# PowerBoard_v9.net
KiCad netlist of a schematic drawn in EAGLE
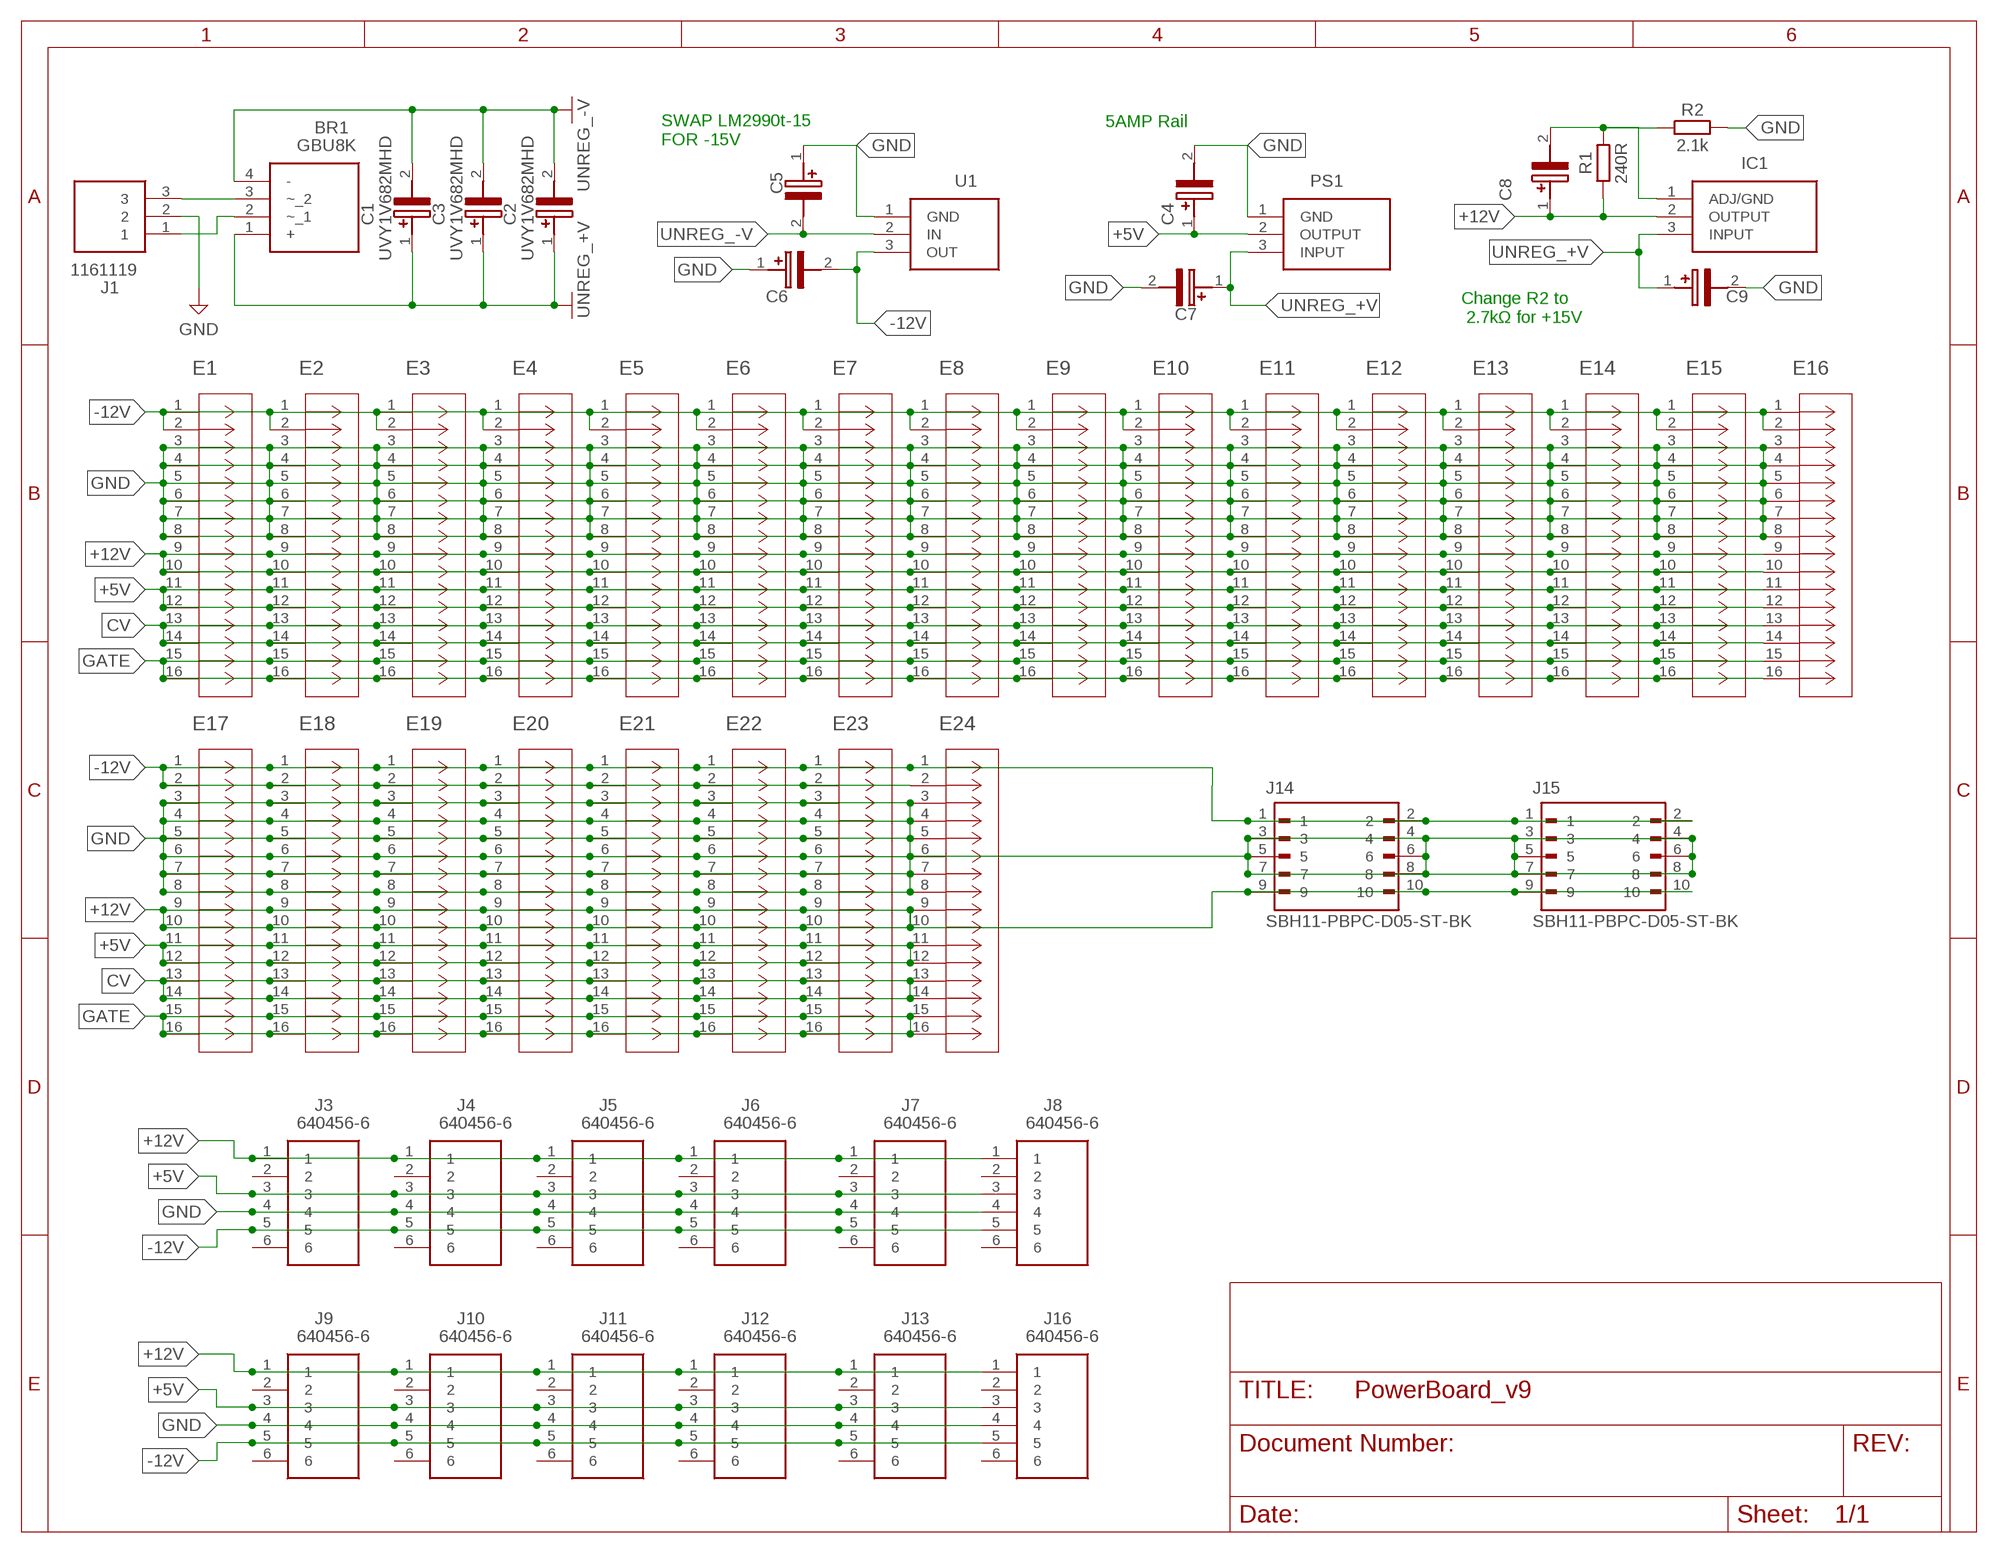
[diagram p0: schematic, sheet 1]

(export (version "E")
  (design (tool "Eeschema 10.0.6"))
  (components
    (comp (ref "BR1")
      (value "GBU8K")
      (footprint "eagle-import:GBU8K")
      (fields (field (name "MOUSER_PART_NUMBER") "512-GBU8K"))
      (libsource (lib "eagle-import") (part "GBU8K"))
    )
    (comp (ref "C1")
      (value "UVY1V682MHD")
      (footprint "eagle-import:CAPPRD750W80D1825H4200")
      (fields (field (name "MOUSER_PART_NUMBER") "647-UVY1V682MHD"))
      (libsource (lib "eagle-import") (part "UVY1V682MHD"))
    )
    (comp (ref "C2")
      (value "UVY1V682MHD")
      (footprint "eagle-import:CAPPRD750W80D1825H4200")
      (fields (field (name "MOUSER_PART_NUMBER") "647-UVY1V682MHD"))
      (libsource (lib "eagle-import") (part "UVY1V682MHD"))
    )
    (comp (ref "C3")
      (value "UVY1V682MHD")
      (footprint "eagle-import:CAPPRD750W80D1825H4200")
      (fields (field (name "MOUSER_PART_NUMBER") "647-UVY1V682MHD"))
      (libsource (lib "eagle-import") (part "UVY1V682MHD"))
    )
    (comp (ref "C4")
      (value "UEP1V101MPD")
      (footprint "eagle-import:CAPPRD500W60D1025H1750")
      (fields (field (name "MOUSER_PART_NUMBER") "647-UEP1V101MPD"))
      (libsource (lib "eagle-import") (part "UEP1V101MPD"))
    )
    (comp (ref "C5")
      (value "UEP1V101MPD")
      (footprint "eagle-import:CAPPRD500W60D1025H1750")
      (fields (field (name "MOUSER_PART_NUMBER") "647-UEP1V101MPD"))
      (libsource (lib "eagle-import") (part "UEP1V101MPD"))
    )
    (comp (ref "C6")
      (value "UEP1V101MPD")
      (footprint "eagle-import:CAPPRD500W60D1025H1750")
      (fields (field (name "MOUSER_PART_NUMBER") "647-UEP1V101MPD"))
      (libsource (lib "eagle-import") (part "UEP1V101MPD"))
    )
    (comp (ref "C7")
      (value "UEP1V101MPD")
      (footprint "eagle-import:CAPPRD500W60D1025H1750")
      (fields (field (name "MOUSER_PART_NUMBER") "647-UEP1V101MPD"))
      (libsource (lib "eagle-import") (part "UEP1V101MPD"))
    )
    (comp (ref "C8")
      (value "UEP1V101MPD")
      (footprint "eagle-import:CAPPRD500W60D1025H1750")
      (fields (field (name "MOUSER_PART_NUMBER") "647-UEP1V101MPD"))
      (libsource (lib "eagle-import") (part "UEP1V101MPD"))
    )
    (comp (ref "C9")
      (value "UEP1V101MPD")
      (footprint "eagle-import:CAPPRD500W60D1025H1750")
      (fields (field (name "MOUSER_PART_NUMBER") "647-UEP1V101MPD"))
      (libsource (lib "eagle-import") (part "UEP1V101MPD"))
    )
    (comp (ref "E1")
      (value "SBH11-PBPC-D08-ST-BKCONN16_SBH11-PBPC-D08-ST-BK_SU")
      (footprint "eagle-import:CONN16_SBH11-PBPC-D08-ST-BK_SU")
      (fields
        (field (name "MANUFACTURER_PART_NUMBER") "SBH11-PBPC-D08-ST-BK")
        (field (name "COPYRIGHT") "Copyright (C) 2025 Ultra Librarian. All rights reserved.")
      )
      (libsource (lib "eagle-import") (part "SBH11-PBPC-D08-ST-BKCONN16_SBH11-PBPC-D08-ST-BK_SU"))
    )
    (comp (ref "E2")
      (value "SBH11-PBPC-D08-ST-BKCONN16_SBH11-PBPC-D08-ST-BK_SU")
      (footprint "eagle-import:CONN16_SBH11-PBPC-D08-ST-BK_SU")
      (fields
        (field (name "MANUFACTURER_PART_NUMBER") "SBH11-PBPC-D08-ST-BK")
        (field (name "COPYRIGHT") "Copyright (C) 2025 Ultra Librarian. All rights reserved.")
      )
      (libsource (lib "eagle-import") (part "SBH11-PBPC-D08-ST-BKCONN16_SBH11-PBPC-D08-ST-BK_SU"))
    )
    (comp (ref "E3")
      (value "SBH11-PBPC-D08-ST-BKCONN16_SBH11-PBPC-D08-ST-BK_SU")
      (footprint "eagle-import:CONN16_SBH11-PBPC-D08-ST-BK_SU")
      (fields
        (field (name "MANUFACTURER_PART_NUMBER") "SBH11-PBPC-D08-ST-BK")
        (field (name "COPYRIGHT") "Copyright (C) 2025 Ultra Librarian. All rights reserved.")
      )
      (libsource (lib "eagle-import") (part "SBH11-PBPC-D08-ST-BKCONN16_SBH11-PBPC-D08-ST-BK_SU"))
    )
    (comp (ref "E4")
      (value "SBH11-PBPC-D08-ST-BKCONN16_SBH11-PBPC-D08-ST-BK_SU")
      (footprint "eagle-import:CONN16_SBH11-PBPC-D08-ST-BK_SU")
      (fields
        (field (name "MANUFACTURER_PART_NUMBER") "SBH11-PBPC-D08-ST-BK")
        (field (name "COPYRIGHT") "Copyright (C) 2025 Ultra Librarian. All rights reserved.")
      )
      (libsource (lib "eagle-import") (part "SBH11-PBPC-D08-ST-BKCONN16_SBH11-PBPC-D08-ST-BK_SU"))
    )
    (comp (ref "E5")
      (value "SBH11-PBPC-D08-ST-BKCONN16_SBH11-PBPC-D08-ST-BK_SU")
      (footprint "eagle-import:CONN16_SBH11-PBPC-D08-ST-BK_SU")
      (fields
        (field (name "MANUFACTURER_PART_NUMBER") "SBH11-PBPC-D08-ST-BK")
        (field (name "COPYRIGHT") "Copyright (C) 2025 Ultra Librarian. All rights reserved.")
      )
      (libsource (lib "eagle-import") (part "SBH11-PBPC-D08-ST-BKCONN16_SBH11-PBPC-D08-ST-BK_SU"))
    )
    (comp (ref "E6")
      (value "SBH11-PBPC-D08-ST-BKCONN16_SBH11-PBPC-D08-ST-BK_SU")
      (footprint "eagle-import:CONN16_SBH11-PBPC-D08-ST-BK_SU")
      (fields
        (field (name "MANUFACTURER_PART_NUMBER") "SBH11-PBPC-D08-ST-BK")
        (field (name "COPYRIGHT") "Copyright (C) 2025 Ultra Librarian. All rights reserved.")
      )
      (libsource (lib "eagle-import") (part "SBH11-PBPC-D08-ST-BKCONN16_SBH11-PBPC-D08-ST-BK_SU"))
    )
    (comp (ref "E7")
      (value "SBH11-PBPC-D08-ST-BKCONN16_SBH11-PBPC-D08-ST-BK_SU")
      (footprint "eagle-import:CONN16_SBH11-PBPC-D08-ST-BK_SU")
      (fields
        (field (name "MANUFACTURER_PART_NUMBER") "SBH11-PBPC-D08-ST-BK")
        (field (name "COPYRIGHT") "Copyright (C) 2025 Ultra Librarian. All rights reserved.")
      )
      (libsource (lib "eagle-import") (part "SBH11-PBPC-D08-ST-BKCONN16_SBH11-PBPC-D08-ST-BK_SU"))
    )
    (comp (ref "E8")
      (value "SBH11-PBPC-D08-ST-BKCONN16_SBH11-PBPC-D08-ST-BK_SU")
      (footprint "eagle-import:CONN16_SBH11-PBPC-D08-ST-BK_SU")
      (fields
        (field (name "MANUFACTURER_PART_NUMBER") "SBH11-PBPC-D08-ST-BK")
        (field (name "COPYRIGHT") "Copyright (C) 2025 Ultra Librarian. All rights reserved.")
      )
      (libsource (lib "eagle-import") (part "SBH11-PBPC-D08-ST-BKCONN16_SBH11-PBPC-D08-ST-BK_SU"))
    )
    (comp (ref "E9")
      (value "SBH11-PBPC-D08-ST-BKCONN16_SBH11-PBPC-D08-ST-BK_SU")
      (footprint "eagle-import:CONN16_SBH11-PBPC-D08-ST-BK_SU")
      (fields
        (field (name "MANUFACTURER_PART_NUMBER") "SBH11-PBPC-D08-ST-BK")
        (field (name "COPYRIGHT") "Copyright (C) 2025 Ultra Librarian. All rights reserved.")
      )
      (libsource (lib "eagle-import") (part "SBH11-PBPC-D08-ST-BKCONN16_SBH11-PBPC-D08-ST-BK_SU"))
    )
    (comp (ref "E10")
      (value "SBH11-PBPC-D08-ST-BKCONN16_SBH11-PBPC-D08-ST-BK_SU")
      (footprint "eagle-import:CONN16_SBH11-PBPC-D08-ST-BK_SU")
      (fields
        (field (name "MANUFACTURER_PART_NUMBER") "SBH11-PBPC-D08-ST-BK")
        (field (name "COPYRIGHT") "Copyright (C) 2025 Ultra Librarian. All rights reserved.")
      )
      (libsource (lib "eagle-import") (part "SBH11-PBPC-D08-ST-BKCONN16_SBH11-PBPC-D08-ST-BK_SU"))
    )
    (comp (ref "E11")
      (value "SBH11-PBPC-D08-ST-BKCONN16_SBH11-PBPC-D08-ST-BK_SU")
      (footprint "eagle-import:CONN16_SBH11-PBPC-D08-ST-BK_SU")
      (fields
        (field (name "MANUFACTURER_PART_NUMBER") "SBH11-PBPC-D08-ST-BK")
        (field (name "COPYRIGHT") "Copyright (C) 2025 Ultra Librarian. All rights reserved.")
      )
      (libsource (lib "eagle-import") (part "SBH11-PBPC-D08-ST-BKCONN16_SBH11-PBPC-D08-ST-BK_SU"))
    )
    (comp (ref "E12")
      (value "SBH11-PBPC-D08-ST-BKCONN16_SBH11-PBPC-D08-ST-BK_SU")
      (footprint "eagle-import:CONN16_SBH11-PBPC-D08-ST-BK_SU")
      (fields
        (field (name "MANUFACTURER_PART_NUMBER") "SBH11-PBPC-D08-ST-BK")
        (field (name "COPYRIGHT") "Copyright (C) 2025 Ultra Librarian. All rights reserved.")
      )
      (libsource (lib "eagle-import") (part "SBH11-PBPC-D08-ST-BKCONN16_SBH11-PBPC-D08-ST-BK_SU"))
    )
    (comp (ref "E13")
      (value "SBH11-PBPC-D08-ST-BKCONN16_SBH11-PBPC-D08-ST-BK_SU")
      (footprint "eagle-import:CONN16_SBH11-PBPC-D08-ST-BK_SU")
      (fields
        (field (name "MANUFACTURER_PART_NUMBER") "SBH11-PBPC-D08-ST-BK")
        (field (name "COPYRIGHT") "Copyright (C) 2025 Ultra Librarian. All rights reserved.")
      )
      (libsource (lib "eagle-import") (part "SBH11-PBPC-D08-ST-BKCONN16_SBH11-PBPC-D08-ST-BK_SU"))
    )
    (comp (ref "E14")
      (value "SBH11-PBPC-D08-ST-BKCONN16_SBH11-PBPC-D08-ST-BK_SU")
      (footprint "eagle-import:CONN16_SBH11-PBPC-D08-ST-BK_SU")
      (fields
        (field (name "MANUFACTURER_PART_NUMBER") "SBH11-PBPC-D08-ST-BK")
        (field (name "COPYRIGHT") "Copyright (C) 2025 Ultra Librarian. All rights reserved.")
      )
      (libsource (lib "eagle-import") (part "SBH11-PBPC-D08-ST-BKCONN16_SBH11-PBPC-D08-ST-BK_SU"))
    )
    (comp (ref "E15")
      (value "SBH11-PBPC-D08-ST-BKCONN16_SBH11-PBPC-D08-ST-BK_SU")
      (footprint "eagle-import:CONN16_SBH11-PBPC-D08-ST-BK_SU")
      (fields
        (field (name "MANUFACTURER_PART_NUMBER") "SBH11-PBPC-D08-ST-BK")
        (field (name "COPYRIGHT") "Copyright (C) 2025 Ultra Librarian. All rights reserved.")
      )
      (libsource (lib "eagle-import") (part "SBH11-PBPC-D08-ST-BKCONN16_SBH11-PBPC-D08-ST-BK_SU"))
    )
    (comp (ref "E16")
      (value "SBH11-PBPC-D08-ST-BKCONN16_SBH11-PBPC-D08-ST-BK_SU")
      (footprint "eagle-import:CONN16_SBH11-PBPC-D08-ST-BK_SU")
      (fields
        (field (name "MANUFACTURER_PART_NUMBER") "SBH11-PBPC-D08-ST-BK")
        (field (name "COPYRIGHT") "Copyright (C) 2025 Ultra Librarian. All rights reserved.")
      )
      (libsource (lib "eagle-import") (part "SBH11-PBPC-D08-ST-BKCONN16_SBH11-PBPC-D08-ST-BK_SU"))
    )
    (comp (ref "E17")
      (value "SBH11-PBPC-D08-ST-BKCONN16_SBH11-PBPC-D08-ST-BK_SU")
      (footprint "eagle-import:CONN16_SBH11-PBPC-D08-ST-BK_SU")
      (fields
        (field (name "MANUFACTURER_PART_NUMBER") "SBH11-PBPC-D08-ST-BK")
        (field (name "COPYRIGHT") "Copyright (C) 2025 Ultra Librarian. All rights reserved.")
      )
      (libsource (lib "eagle-import") (part "SBH11-PBPC-D08-ST-BKCONN16_SBH11-PBPC-D08-ST-BK_SU"))
    )
    (comp (ref "E18")
      (value "SBH11-PBPC-D08-ST-BKCONN16_SBH11-PBPC-D08-ST-BK_SU")
      (footprint "eagle-import:CONN16_SBH11-PBPC-D08-ST-BK_SU")
      (fields
        (field (name "MANUFACTURER_PART_NUMBER") "SBH11-PBPC-D08-ST-BK")
        (field (name "COPYRIGHT") "Copyright (C) 2025 Ultra Librarian. All rights reserved.")
      )
      (libsource (lib "eagle-import") (part "SBH11-PBPC-D08-ST-BKCONN16_SBH11-PBPC-D08-ST-BK_SU"))
    )
    (comp (ref "E19")
      (value "SBH11-PBPC-D08-ST-BKCONN16_SBH11-PBPC-D08-ST-BK_SU")
      (footprint "eagle-import:CONN16_SBH11-PBPC-D08-ST-BK_SU")
      (fields
        (field (name "MANUFACTURER_PART_NUMBER") "SBH11-PBPC-D08-ST-BK")
        (field (name "COPYRIGHT") "Copyright (C) 2025 Ultra Librarian. All rights reserved.")
      )
      (libsource (lib "eagle-import") (part "SBH11-PBPC-D08-ST-BKCONN16_SBH11-PBPC-D08-ST-BK_SU"))
    )
    (comp (ref "E20")
      (value "SBH11-PBPC-D08-ST-BKCONN16_SBH11-PBPC-D08-ST-BK_SU")
      (footprint "eagle-import:CONN16_SBH11-PBPC-D08-ST-BK_SU")
      (fields
        (field (name "MANUFACTURER_PART_NUMBER") "SBH11-PBPC-D08-ST-BK")
        (field (name "COPYRIGHT") "Copyright (C) 2025 Ultra Librarian. All rights reserved.")
      )
      (libsource (lib "eagle-import") (part "SBH11-PBPC-D08-ST-BKCONN16_SBH11-PBPC-D08-ST-BK_SU"))
    )
    (comp (ref "E21")
      (value "SBH11-PBPC-D08-ST-BKCONN16_SBH11-PBPC-D08-ST-BK_SU")
      (footprint "eagle-import:CONN16_SBH11-PBPC-D08-ST-BK_SU")
      (fields
        (field (name "MANUFACTURER_PART_NUMBER") "SBH11-PBPC-D08-ST-BK")
        (field (name "COPYRIGHT") "Copyright (C) 2025 Ultra Librarian. All rights reserved.")
      )
      (libsource (lib "eagle-import") (part "SBH11-PBPC-D08-ST-BKCONN16_SBH11-PBPC-D08-ST-BK_SU"))
    )
    (comp (ref "E22")
      (value "SBH11-PBPC-D08-ST-BKCONN16_SBH11-PBPC-D08-ST-BK_SU")
      (footprint "eagle-import:CONN16_SBH11-PBPC-D08-ST-BK_SU")
      (fields
        (field (name "MANUFACTURER_PART_NUMBER") "SBH11-PBPC-D08-ST-BK")
        (field (name "COPYRIGHT") "Copyright (C) 2025 Ultra Librarian. All rights reserved.")
      )
      (libsource (lib "eagle-import") (part "SBH11-PBPC-D08-ST-BKCONN16_SBH11-PBPC-D08-ST-BK_SU"))
    )
    (comp (ref "E23")
      (value "SBH11-PBPC-D08-ST-BKCONN16_SBH11-PBPC-D08-ST-BK_SU")
      (footprint "eagle-import:CONN16_SBH11-PBPC-D08-ST-BK_SU")
      (fields
        (field (name "MANUFACTURER_PART_NUMBER") "SBH11-PBPC-D08-ST-BK")
        (field (name "COPYRIGHT") "Copyright (C) 2025 Ultra Librarian. All rights reserved.")
      )
      (libsource (lib "eagle-import") (part "SBH11-PBPC-D08-ST-BKCONN16_SBH11-PBPC-D08-ST-BK_SU"))
    )
    (comp (ref "E24")
      (value "SBH11-PBPC-D08-ST-BKCONN16_SBH11-PBPC-D08-ST-BK_SU")
      (footprint "eagle-import:CONN16_SBH11-PBPC-D08-ST-BK_SU")
      (fields
        (field (name "MANUFACTURER_PART_NUMBER") "SBH11-PBPC-D08-ST-BK")
        (field (name "COPYRIGHT") "Copyright (C) 2025 Ultra Librarian. All rights reserved.")
      )
      (libsource (lib "eagle-import") (part "SBH11-PBPC-D08-ST-BKCONN16_SBH11-PBPC-D08-ST-BK_SU"))
    )
    (comp (ref "IC1")
      (value "LM1084IT-ADJ_NOPB")
      (footprint "eagle-import:TO254P470X1028X1955-3P")
      (fields
        (field (name "MANUFACTURER_PART_NUMBER") "LM1084IT-ADJ/NOPB")
        (field (name "MOUSER_PART_NUMBER") "926-LM1084IT-ADJNOPB")
      )
      (libsource (lib "eagle-import") (part "LM1084IT-ADJ_NOPB"))
    )
    (comp (ref "J1")
      (value "1161119")
      (footprint "eagle-import:1161119")
      (fields (field (name "MOUSER_PART_NUMBER") "651-1161119"))
      (libsource (lib "eagle-import") (part "1161119"))
    )
    (comp (ref "J3")
      (value "640456-6")
      (footprint "eagle-import:SHDR6W66P0X254_1X6_1524X572X10")
      (fields (field (name "MOUSER_PART_NUMBER") "571-6404566"))
      (libsource (lib "eagle-import") (part "640456-6"))
    )
    (comp (ref "J4")
      (value "640456-6")
      (footprint "eagle-import:SHDR6W66P0X254_1X6_1524X572X10")
      (fields (field (name "MOUSER_PART_NUMBER") "571-6404566"))
      (libsource (lib "eagle-import") (part "640456-6"))
    )
    (comp (ref "J5")
      (value "640456-6")
      (footprint "eagle-import:SHDR6W66P0X254_1X6_1524X572X10")
      (fields (field (name "MOUSER_PART_NUMBER") "571-6404566"))
      (libsource (lib "eagle-import") (part "640456-6"))
    )
    (comp (ref "J6")
      (value "640456-6")
      (footprint "eagle-import:SHDR6W66P0X254_1X6_1524X572X10")
      (fields (field (name "MOUSER_PART_NUMBER") "571-6404566"))
      (libsource (lib "eagle-import") (part "640456-6"))
    )
    (comp (ref "J7")
      (value "640456-6")
      (footprint "eagle-import:SHDR6W66P0X254_1X6_1524X572X10")
      (fields (field (name "MOUSER_PART_NUMBER") "571-6404566"))
      (libsource (lib "eagle-import") (part "640456-6"))
    )
    (comp (ref "J8")
      (value "640456-6")
      (footprint "eagle-import:SHDR6W66P0X254_1X6_1524X572X10")
      (fields (field (name "MOUSER_PART_NUMBER") "571-6404566"))
      (libsource (lib "eagle-import") (part "640456-6"))
    )
    (comp (ref "J9")
      (value "640456-6")
      (footprint "eagle-import:SHDR6W66P0X254_1X6_1524X572X10")
      (fields (field (name "MOUSER_PART_NUMBER") "571-6404566"))
      (libsource (lib "eagle-import") (part "640456-6"))
    )
    (comp (ref "J10")
      (value "640456-6")
      (footprint "eagle-import:SHDR6W66P0X254_1X6_1524X572X10")
      (fields (field (name "MOUSER_PART_NUMBER") "571-6404566"))
      (libsource (lib "eagle-import") (part "640456-6"))
    )
    (comp (ref "J11")
      (value "640456-6")
      (footprint "eagle-import:SHDR6W66P0X254_1X6_1524X572X10")
      (fields (field (name "MOUSER_PART_NUMBER") "571-6404566"))
      (libsource (lib "eagle-import") (part "640456-6"))
    )
    (comp (ref "J12")
      (value "640456-6")
      (footprint "eagle-import:SHDR6W66P0X254_1X6_1524X572X10")
      (fields (field (name "MOUSER_PART_NUMBER") "571-6404566"))
      (libsource (lib "eagle-import") (part "640456-6"))
    )
    (comp (ref "J13")
      (value "640456-6")
      (footprint "eagle-import:SHDR6W66P0X254_1X6_1524X572X10")
      (fields (field (name "MOUSER_PART_NUMBER") "571-6404566"))
      (libsource (lib "eagle-import") (part "640456-6"))
    )
    (comp (ref "J14")
      (value "SBH11-PBPC-D05-ST-BK")
      (footprint "eagle-import:SULLINS_SBH11-PBPC-D05-ST-BK")
      (fields (field (name "MANUFACTURER") "Sullins Connector Solutions"))
      (libsource (lib "eagle-import") (part "SBH11-PBPC-D05-ST-BK"))
    )
    (comp (ref "J15")
      (value "SBH11-PBPC-D05-ST-BK")
      (footprint "eagle-import:SULLINS_SBH11-PBPC-D05-ST-BK")
      (fields (field (name "MANUFACTURER") "Sullins Connector Solutions"))
      (libsource (lib "eagle-import") (part "SBH11-PBPC-D05-ST-BK"))
    )
    (comp (ref "J16")
      (value "640456-6")
      (footprint "eagle-import:SHDR6W66P0X254_1X6_1524X572X10")
      (fields (field (name "MOUSER_PART_NUMBER") "571-6404566"))
      (libsource (lib "eagle-import") (part "640456-6"))
    )
    (comp (ref "PS1")
      (value "LM1084IT-5.0_NOPB")
      (footprint "eagle-import:TO254P470X1028X1955-3P")
      (fields
        (field (name "MANUFACTURER_PART_NUMBER") "LM1084IT-5.0/NOPB")
        (field (name "MOUSER_PART_NUMBER") "926-LM1084IT50NOPB")
      )
      (libsource (lib "eagle-import") (part "LM1084IT-5.0_NOPB"))
    )
    (comp (ref "R1")
      (value "240R")
      (footprint "eagle-import:RESAD724W46L381D178B")
      (libsource (lib "eagle-import") (part "RESISTOR_AXIAL-7.2MM-PITCH_"))
    )
    (comp (ref "R2")
      (value "2.1k")
      (footprint "eagle-import:RESAD724W46L381D178B")
      (libsource (lib "eagle-import") (part "RESISTOR_AXIAL-7.2MM-PITCH_"))
    )
    (comp (ref "U1")
      (value "LM2990T-12_NOPB")
      (footprint "eagle-import:TO254P470X1028X1955-3P")
      (fields
        (field (name "MANUFACTURER_PART_NUMBER") "LM2990T-12/NOPB")
        (field (name "MOUSER_PART_NUMBER") "926-LM2990T-12/NOPB")
      )
      (libsource (lib "eagle-import") (part "LM2990T-12_NOPB"))
    )
  )
  (nets
    (net (code "1") (name "+5V") (class "Default")
      (node (ref "C4") (pin "1") (pinfunction "+_1") (pintype "bidirectional"))
      (node (ref "E1") (pin "11") (pinfunction "11_11") (pintype "passive"))
      (node (ref "E1") (pin "12") (pinfunction "12_12") (pintype "passive"))
      (node (ref "E10") (pin "11") (pinfunction "11_11") (pintype "passive"))
      (node (ref "E10") (pin "12") (pinfunction "12_12") (pintype "passive"))
      (node (ref "E11") (pin "11") (pinfunction "11_11") (pintype "passive"))
      (node (ref "E11") (pin "12") (pinfunction "12_12") (pintype "passive"))
      (node (ref "E12") (pin "11") (pinfunction "11_11") (pintype "passive"))
      (node (ref "E12") (pin "12") (pinfunction "12_12") (pintype "passive"))
      (node (ref "E13") (pin "11") (pinfunction "11_11") (pintype "passive"))
      (node (ref "E13") (pin "12") (pinfunction "12_12") (pintype "passive"))
      (node (ref "E14") (pin "11") (pinfunction "11_11") (pintype "passive"))
      (node (ref "E14") (pin "12") (pinfunction "12_12") (pintype "passive"))
      (node (ref "E15") (pin "11") (pinfunction "11_11") (pintype "passive"))
      (node (ref "E15") (pin "12") (pinfunction "12_12") (pintype "passive"))
      (node (ref "E16") (pin "11") (pinfunction "11_11") (pintype "passive"))
      (node (ref "E16") (pin "12") (pinfunction "12_12") (pintype "passive"))
      (node (ref "E17") (pin "11") (pinfunction "11_11") (pintype "passive"))
      (node (ref "E17") (pin "12") (pinfunction "12_12") (pintype "passive"))
      (node (ref "E18") (pin "11") (pinfunction "11_11") (pintype "passive"))
      (node (ref "E18") (pin "12") (pinfunction "12_12") (pintype "passive"))
      (node (ref "E19") (pin "11") (pinfunction "11_11") (pintype "passive"))
      (node (ref "E19") (pin "12") (pinfunction "12_12") (pintype "passive"))
      (node (ref "E2") (pin "11") (pinfunction "11_11") (pintype "passive"))
      (node (ref "E2") (pin "12") (pinfunction "12_12") (pintype "passive"))
      (node (ref "E20") (pin "11") (pinfunction "11_11") (pintype "passive"))
      (node (ref "E20") (pin "12") (pinfunction "12_12") (pintype "passive"))
      (node (ref "E21") (pin "11") (pinfunction "11_11") (pintype "passive"))
      (node (ref "E21") (pin "12") (pinfunction "12_12") (pintype "passive"))
      (node (ref "E22") (pin "11") (pinfunction "11_11") (pintype "passive"))
      (node (ref "E22") (pin "12") (pinfunction "12_12") (pintype "passive"))
      (node (ref "E23") (pin "11") (pinfunction "11_11") (pintype "passive"))
      (node (ref "E23") (pin "12") (pinfunction "12_12") (pintype "passive"))
      (node (ref "E24") (pin "11") (pinfunction "11_11") (pintype "passive"))
      (node (ref "E24") (pin "12") (pinfunction "12_12") (pintype "passive"))
      (node (ref "E3") (pin "11") (pinfunction "11_11") (pintype "passive"))
      (node (ref "E3") (pin "12") (pinfunction "12_12") (pintype "passive"))
      (node (ref "E4") (pin "11") (pinfunction "11_11") (pintype "passive"))
      (node (ref "E4") (pin "12") (pinfunction "12_12") (pintype "passive"))
      (node (ref "E5") (pin "11") (pinfunction "11_11") (pintype "passive"))
      (node (ref "E5") (pin "12") (pinfunction "12_12") (pintype "passive"))
      (node (ref "E6") (pin "11") (pinfunction "11_11") (pintype "passive"))
      (node (ref "E6") (pin "12") (pinfunction "12_12") (pintype "passive"))
      (node (ref "E7") (pin "11") (pinfunction "11_11") (pintype "passive"))
      (node (ref "E7") (pin "12") (pinfunction "12_12") (pintype "passive"))
      (node (ref "E8") (pin "11") (pinfunction "11_11") (pintype "passive"))
      (node (ref "E8") (pin "12") (pinfunction "12_12") (pintype "passive"))
      (node (ref "E9") (pin "11") (pinfunction "11_11") (pintype "passive"))
      (node (ref "E9") (pin "12") (pinfunction "12_12") (pintype "passive"))
      (node (ref "J10") (pin "3") (pinfunction "3_3") (pintype "bidirectional"))
      (node (ref "J11") (pin "3") (pinfunction "3_3") (pintype "bidirectional"))
      (node (ref "J12") (pin "3") (pinfunction "3_3") (pintype "bidirectional"))
      (node (ref "J13") (pin "3") (pinfunction "3_3") (pintype "bidirectional"))
      (node (ref "J16") (pin "3") (pinfunction "3_3") (pintype "bidirectional"))
      (node (ref "J3") (pin "3") (pinfunction "3_3") (pintype "bidirectional"))
      (node (ref "J4") (pin "3") (pinfunction "3_3") (pintype "bidirectional"))
      (node (ref "J5") (pin "3") (pinfunction "3_3") (pintype "bidirectional"))
      (node (ref "J6") (pin "3") (pinfunction "3_3") (pintype "bidirectional"))
      (node (ref "J7") (pin "3") (pinfunction "3_3") (pintype "bidirectional"))
      (node (ref "J8") (pin "3") (pinfunction "3_3") (pintype "bidirectional"))
      (node (ref "J9") (pin "3") (pinfunction "3_3") (pintype "bidirectional"))
      (node (ref "PS1") (pin "2") (pinfunction "OUTPUT_2") (pintype "output"))
    )
    (net (code "2") (name "+12V") (class "Default")
      (node (ref "C8") (pin "1") (pinfunction "+_1") (pintype "bidirectional"))
      (node (ref "E1") (pin "10") (pinfunction "10_10") (pintype "passive"))
      (node (ref "E1") (pin "9") (pinfunction "9_9") (pintype "passive"))
      (node (ref "E10") (pin "10") (pinfunction "10_10") (pintype "passive"))
      (node (ref "E10") (pin "9") (pinfunction "9_9") (pintype "passive"))
      (node (ref "E11") (pin "10") (pinfunction "10_10") (pintype "passive"))
      (node (ref "E11") (pin "9") (pinfunction "9_9") (pintype "passive"))
      (node (ref "E12") (pin "10") (pinfunction "10_10") (pintype "passive"))
      (node (ref "E12") (pin "9") (pinfunction "9_9") (pintype "passive"))
      (node (ref "E13") (pin "10") (pinfunction "10_10") (pintype "passive"))
      (node (ref "E13") (pin "9") (pinfunction "9_9") (pintype "passive"))
      (node (ref "E14") (pin "10") (pinfunction "10_10") (pintype "passive"))
      (node (ref "E14") (pin "9") (pinfunction "9_9") (pintype "passive"))
      (node (ref "E15") (pin "10") (pinfunction "10_10") (pintype "passive"))
      (node (ref "E15") (pin "9") (pinfunction "9_9") (pintype "passive"))
      (node (ref "E16") (pin "10") (pinfunction "10_10") (pintype "passive"))
      (node (ref "E16") (pin "9") (pinfunction "9_9") (pintype "passive"))
      (node (ref "E17") (pin "10") (pinfunction "10_10") (pintype "passive"))
      (node (ref "E17") (pin "9") (pinfunction "9_9") (pintype "passive"))
      (node (ref "E18") (pin "10") (pinfunction "10_10") (pintype "passive"))
      (node (ref "E18") (pin "9") (pinfunction "9_9") (pintype "passive"))
      (node (ref "E19") (pin "10") (pinfunction "10_10") (pintype "passive"))
      (node (ref "E19") (pin "9") (pinfunction "9_9") (pintype "passive"))
      (node (ref "E2") (pin "10") (pinfunction "10_10") (pintype "passive"))
      (node (ref "E2") (pin "9") (pinfunction "9_9") (pintype "passive"))
      (node (ref "E20") (pin "10") (pinfunction "10_10") (pintype "passive"))
      (node (ref "E20") (pin "9") (pinfunction "9_9") (pintype "passive"))
      (node (ref "E21") (pin "10") (pinfunction "10_10") (pintype "passive"))
      (node (ref "E21") (pin "9") (pinfunction "9_9") (pintype "passive"))
      (node (ref "E22") (pin "10") (pinfunction "10_10") (pintype "passive"))
      (node (ref "E22") (pin "9") (pinfunction "9_9") (pintype "passive"))
      (node (ref "E23") (pin "10") (pinfunction "10_10") (pintype "passive"))
      (node (ref "E23") (pin "9") (pinfunction "9_9") (pintype "passive"))
      (node (ref "E24") (pin "10") (pinfunction "10_10") (pintype "passive"))
      (node (ref "E24") (pin "9") (pinfunction "9_9") (pintype "passive"))
      (node (ref "E3") (pin "10") (pinfunction "10_10") (pintype "passive"))
      (node (ref "E3") (pin "9") (pinfunction "9_9") (pintype "passive"))
      (node (ref "E4") (pin "10") (pinfunction "10_10") (pintype "passive"))
      (node (ref "E4") (pin "9") (pinfunction "9_9") (pintype "passive"))
      (node (ref "E5") (pin "10") (pinfunction "10_10") (pintype "passive"))
      (node (ref "E5") (pin "9") (pinfunction "9_9") (pintype "passive"))
      (node (ref "E6") (pin "10") (pinfunction "10_10") (pintype "passive"))
      (node (ref "E6") (pin "9") (pinfunction "9_9") (pintype "passive"))
      (node (ref "E7") (pin "10") (pinfunction "10_10") (pintype "passive"))
      (node (ref "E7") (pin "9") (pinfunction "9_9") (pintype "passive"))
      (node (ref "E8") (pin "10") (pinfunction "10_10") (pintype "passive"))
      (node (ref "E8") (pin "9") (pinfunction "9_9") (pintype "passive"))
      (node (ref "E9") (pin "10") (pinfunction "10_10") (pintype "passive"))
      (node (ref "E9") (pin "9") (pinfunction "9_9") (pintype "passive"))
      (node (ref "IC1") (pin "2") (pinfunction "OUTPUT_2") (pintype "bidirectional"))
      (node (ref "J10") (pin "1") (pinfunction "1_1") (pintype "bidirectional"))
      (node (ref "J11") (pin "1") (pinfunction "1_1") (pintype "bidirectional"))
      (node (ref "J12") (pin "1") (pinfunction "1_1") (pintype "bidirectional"))
      (node (ref "J13") (pin "1") (pinfunction "1_1") (pintype "bidirectional"))
      (node (ref "J14") (pin "10") (pinfunction "10_10") (pintype "passive"))
      (node (ref "J14") (pin "9") (pinfunction "9_9") (pintype "passive"))
      (node (ref "J15") (pin "10") (pinfunction "10_10") (pintype "passive"))
      (node (ref "J15") (pin "9") (pinfunction "9_9") (pintype "passive"))
      (node (ref "J16") (pin "1") (pinfunction "1_1") (pintype "bidirectional"))
      (node (ref "J3") (pin "1") (pinfunction "1_1") (pintype "bidirectional"))
      (node (ref "J4") (pin "1") (pinfunction "1_1") (pintype "bidirectional"))
      (node (ref "J5") (pin "1") (pinfunction "1_1") (pintype "bidirectional"))
      (node (ref "J6") (pin "1") (pinfunction "1_1") (pintype "bidirectional"))
      (node (ref "J7") (pin "1") (pinfunction "1_1") (pintype "bidirectional"))
      (node (ref "J8") (pin "1") (pinfunction "1_1") (pintype "bidirectional"))
      (node (ref "J9") (pin "1") (pinfunction "1_1") (pintype "bidirectional"))
      (node (ref "R1") (pin "1") (pinfunction "1_1") (pintype "passive"))
    )
    (net (code "3") (name "-12V") (class "Default")
      (node (ref "C6") (pin "2") (pinfunction "-_2") (pintype "bidirectional"))
      (node (ref "E1") (pin "1") (pinfunction "1_1") (pintype "passive"))
      (node (ref "E1") (pin "2") (pinfunction "2_2") (pintype "passive"))
      (node (ref "E10") (pin "1") (pinfunction "1_1") (pintype "passive"))
      (node (ref "E10") (pin "2") (pinfunction "2_2") (pintype "passive"))
      (node (ref "E11") (pin "1") (pinfunction "1_1") (pintype "passive"))
      (node (ref "E11") (pin "2") (pinfunction "2_2") (pintype "passive"))
      (node (ref "E12") (pin "1") (pinfunction "1_1") (pintype "passive"))
      (node (ref "E12") (pin "2") (pinfunction "2_2") (pintype "passive"))
      (node (ref "E13") (pin "1") (pinfunction "1_1") (pintype "passive"))
      (node (ref "E13") (pin "2") (pinfunction "2_2") (pintype "passive"))
      (node (ref "E14") (pin "1") (pinfunction "1_1") (pintype "passive"))
      (node (ref "E14") (pin "2") (pinfunction "2_2") (pintype "passive"))
      (node (ref "E15") (pin "1") (pinfunction "1_1") (pintype "passive"))
      (node (ref "E15") (pin "2") (pinfunction "2_2") (pintype "passive"))
      (node (ref "E16") (pin "1") (pinfunction "1_1") (pintype "passive"))
      (node (ref "E16") (pin "2") (pinfunction "2_2") (pintype "passive"))
      (node (ref "E17") (pin "1") (pinfunction "1_1") (pintype "passive"))
      (node (ref "E17") (pin "2") (pinfunction "2_2") (pintype "passive"))
      (node (ref "E18") (pin "1") (pinfunction "1_1") (pintype "passive"))
      (node (ref "E18") (pin "2") (pinfunction "2_2") (pintype "passive"))
      (node (ref "E19") (pin "1") (pinfunction "1_1") (pintype "passive"))
      (node (ref "E19") (pin "2") (pinfunction "2_2") (pintype "passive"))
      (node (ref "E2") (pin "1") (pinfunction "1_1") (pintype "passive"))
      (node (ref "E2") (pin "2") (pinfunction "2_2") (pintype "passive"))
      (node (ref "E20") (pin "1") (pinfunction "1_1") (pintype "passive"))
      (node (ref "E20") (pin "2") (pinfunction "2_2") (pintype "passive"))
      (node (ref "E21") (pin "1") (pinfunction "1_1") (pintype "passive"))
      (node (ref "E21") (pin "2") (pinfunction "2_2") (pintype "passive"))
      (node (ref "E22") (pin "1") (pinfunction "1_1") (pintype "passive"))
      (node (ref "E22") (pin "2") (pinfunction "2_2") (pintype "passive"))
      (node (ref "E23") (pin "1") (pinfunction "1_1") (pintype "passive"))
      (node (ref "E23") (pin "2") (pinfunction "2_2") (pintype "passive"))
      (node (ref "E24") (pin "1") (pinfunction "1_1") (pintype "passive"))
      (node (ref "E24") (pin "2") (pinfunction "2_2") (pintype "passive"))
      (node (ref "E3") (pin "1") (pinfunction "1_1") (pintype "passive"))
      (node (ref "E3") (pin "2") (pinfunction "2_2") (pintype "passive"))
      (node (ref "E4") (pin "1") (pinfunction "1_1") (pintype "passive"))
      (node (ref "E4") (pin "2") (pinfunction "2_2") (pintype "passive"))
      (node (ref "E5") (pin "1") (pinfunction "1_1") (pintype "passive"))
      (node (ref "E5") (pin "2") (pinfunction "2_2") (pintype "passive"))
      (node (ref "E6") (pin "1") (pinfunction "1_1") (pintype "passive"))
      (node (ref "E6") (pin "2") (pinfunction "2_2") (pintype "passive"))
      (node (ref "E7") (pin "1") (pinfunction "1_1") (pintype "passive"))
      (node (ref "E7") (pin "2") (pinfunction "2_2") (pintype "passive"))
      (node (ref "E8") (pin "1") (pinfunction "1_1") (pintype "passive"))
      (node (ref "E8") (pin "2") (pinfunction "2_2") (pintype "passive"))
      (node (ref "E9") (pin "1") (pinfunction "1_1") (pintype "passive"))
      (node (ref "E9") (pin "2") (pinfunction "2_2") (pintype "passive"))
      (node (ref "J10") (pin "5") (pinfunction "5_5") (pintype "bidirectional"))
      (node (ref "J11") (pin "5") (pinfunction "5_5") (pintype "bidirectional"))
      (node (ref "J12") (pin "5") (pinfunction "5_5") (pintype "bidirectional"))
      (node (ref "J13") (pin "5") (pinfunction "5_5") (pintype "bidirectional"))
      (node (ref "J14") (pin "1") (pinfunction "1_1") (pintype "passive"))
      (node (ref "J14") (pin "2") (pinfunction "2_2") (pintype "passive"))
      (node (ref "J15") (pin "1") (pinfunction "1_1") (pintype "passive"))
      (node (ref "J15") (pin "2") (pinfunction "2_2") (pintype "passive"))
      (node (ref "J16") (pin "5") (pinfunction "5_5") (pintype "bidirectional"))
      (node (ref "J3") (pin "5") (pinfunction "5_5") (pintype "bidirectional"))
      (node (ref "J4") (pin "5") (pinfunction "5_5") (pintype "bidirectional"))
      (node (ref "J5") (pin "5") (pinfunction "5_5") (pintype "bidirectional"))
      (node (ref "J6") (pin "5") (pinfunction "5_5") (pintype "bidirectional"))
      (node (ref "J7") (pin "5") (pinfunction "5_5") (pintype "bidirectional"))
      (node (ref "J8") (pin "5") (pinfunction "5_5") (pintype "bidirectional"))
      (node (ref "J9") (pin "5") (pinfunction "5_5") (pintype "bidirectional"))
      (node (ref "U1") (pin "3") (pinfunction "OUT_3") (pintype "bidirectional"))
    )
    (net (code "4") (name "CV") (class "Default")
      (node (ref "E1") (pin "13") (pinfunction "13_13") (pintype "passive"))
      (node (ref "E1") (pin "14") (pinfunction "14_14") (pintype "passive"))
      (node (ref "E10") (pin "13") (pinfunction "13_13") (pintype "passive"))
      (node (ref "E10") (pin "14") (pinfunction "14_14") (pintype "passive"))
      (node (ref "E11") (pin "13") (pinfunction "13_13") (pintype "passive"))
      (node (ref "E11") (pin "14") (pinfunction "14_14") (pintype "passive"))
      (node (ref "E12") (pin "13") (pinfunction "13_13") (pintype "passive"))
      (node (ref "E12") (pin "14") (pinfunction "14_14") (pintype "passive"))
      (node (ref "E13") (pin "13") (pinfunction "13_13") (pintype "passive"))
      (node (ref "E13") (pin "14") (pinfunction "14_14") (pintype "passive"))
      (node (ref "E14") (pin "13") (pinfunction "13_13") (pintype "passive"))
      (node (ref "E14") (pin "14") (pinfunction "14_14") (pintype "passive"))
      (node (ref "E15") (pin "13") (pinfunction "13_13") (pintype "passive"))
      (node (ref "E15") (pin "14") (pinfunction "14_14") (pintype "passive"))
      (node (ref "E16") (pin "13") (pinfunction "13_13") (pintype "passive"))
      (node (ref "E16") (pin "14") (pinfunction "14_14") (pintype "passive"))
      (node (ref "E17") (pin "13") (pinfunction "13_13") (pintype "passive"))
      (node (ref "E17") (pin "14") (pinfunction "14_14") (pintype "passive"))
      (node (ref "E18") (pin "13") (pinfunction "13_13") (pintype "passive"))
      (node (ref "E18") (pin "14") (pinfunction "14_14") (pintype "passive"))
      (node (ref "E19") (pin "13") (pinfunction "13_13") (pintype "passive"))
      (node (ref "E19") (pin "14") (pinfunction "14_14") (pintype "passive"))
      (node (ref "E2") (pin "13") (pinfunction "13_13") (pintype "passive"))
      (node (ref "E2") (pin "14") (pinfunction "14_14") (pintype "passive"))
      (node (ref "E20") (pin "13") (pinfunction "13_13") (pintype "passive"))
      (node (ref "E20") (pin "14") (pinfunction "14_14") (pintype "passive"))
      (node (ref "E21") (pin "13") (pinfunction "13_13") (pintype "passive"))
      (node (ref "E21") (pin "14") (pinfunction "14_14") (pintype "passive"))
      (node (ref "E22") (pin "13") (pinfunction "13_13") (pintype "passive"))
      (node (ref "E22") (pin "14") (pinfunction "14_14") (pintype "passive"))
      (node (ref "E23") (pin "13") (pinfunction "13_13") (pintype "passive"))
      (node (ref "E23") (pin "14") (pinfunction "14_14") (pintype "passive"))
      (node (ref "E24") (pin "13") (pinfunction "13_13") (pintype "passive"))
      (node (ref "E24") (pin "14") (pinfunction "14_14") (pintype "passive"))
      (node (ref "E3") (pin "13") (pinfunction "13_13") (pintype "passive"))
      (node (ref "E3") (pin "14") (pinfunction "14_14") (pintype "passive"))
      (node (ref "E4") (pin "13") (pinfunction "13_13") (pintype "passive"))
      (node (ref "E4") (pin "14") (pinfunction "14_14") (pintype "passive"))
      (node (ref "E5") (pin "13") (pinfunction "13_13") (pintype "passive"))
      (node (ref "E5") (pin "14") (pinfunction "14_14") (pintype "passive"))
      (node (ref "E6") (pin "13") (pinfunction "13_13") (pintype "passive"))
      (node (ref "E6") (pin "14") (pinfunction "14_14") (pintype "passive"))
      (node (ref "E7") (pin "13") (pinfunction "13_13") (pintype "passive"))
      (node (ref "E7") (pin "14") (pinfunction "14_14") (pintype "passive"))
      (node (ref "E8") (pin "13") (pinfunction "13_13") (pintype "passive"))
      (node (ref "E8") (pin "14") (pinfunction "14_14") (pintype "passive"))
      (node (ref "E9") (pin "13") (pinfunction "13_13") (pintype "passive"))
      (node (ref "E9") (pin "14") (pinfunction "14_14") (pintype "passive"))
    )
    (net (code "5") (name "GATE") (class "Default")
      (node (ref "E1") (pin "15") (pinfunction "15_15") (pintype "passive"))
      (node (ref "E1") (pin "16") (pinfunction "16_16") (pintype "passive"))
      (node (ref "E10") (pin "15") (pinfunction "15_15") (pintype "passive"))
      (node (ref "E10") (pin "16") (pinfunction "16_16") (pintype "passive"))
      (node (ref "E11") (pin "15") (pinfunction "15_15") (pintype "passive"))
      (node (ref "E11") (pin "16") (pinfunction "16_16") (pintype "passive"))
      (node (ref "E12") (pin "15") (pinfunction "15_15") (pintype "passive"))
      (node (ref "E12") (pin "16") (pinfunction "16_16") (pintype "passive"))
      (node (ref "E13") (pin "15") (pinfunction "15_15") (pintype "passive"))
      (node (ref "E13") (pin "16") (pinfunction "16_16") (pintype "passive"))
      (node (ref "E14") (pin "15") (pinfunction "15_15") (pintype "passive"))
      (node (ref "E14") (pin "16") (pinfunction "16_16") (pintype "passive"))
      (node (ref "E15") (pin "15") (pinfunction "15_15") (pintype "passive"))
      (node (ref "E15") (pin "16") (pinfunction "16_16") (pintype "passive"))
      (node (ref "E16") (pin "15") (pinfunction "15_15") (pintype "passive"))
      (node (ref "E16") (pin "16") (pinfunction "16_16") (pintype "passive"))
      (node (ref "E17") (pin "15") (pinfunction "15_15") (pintype "passive"))
      (node (ref "E17") (pin "16") (pinfunction "16_16") (pintype "passive"))
      (node (ref "E18") (pin "15") (pinfunction "15_15") (pintype "passive"))
      (node (ref "E18") (pin "16") (pinfunction "16_16") (pintype "passive"))
      (node (ref "E19") (pin "15") (pinfunction "15_15") (pintype "passive"))
      (node (ref "E19") (pin "16") (pinfunction "16_16") (pintype "passive"))
      (node (ref "E2") (pin "15") (pinfunction "15_15") (pintype "passive"))
      (node (ref "E2") (pin "16") (pinfunction "16_16") (pintype "passive"))
      (node (ref "E20") (pin "15") (pinfunction "15_15") (pintype "passive"))
      (node (ref "E20") (pin "16") (pinfunction "16_16") (pintype "passive"))
      (node (ref "E21") (pin "15") (pinfunction "15_15") (pintype "passive"))
      (node (ref "E21") (pin "16") (pinfunction "16_16") (pintype "passive"))
      (node (ref "E22") (pin "15") (pinfunction "15_15") (pintype "passive"))
      (node (ref "E22") (pin "16") (pinfunction "16_16") (pintype "passive"))
      (node (ref "E23") (pin "15") (pinfunction "15_15") (pintype "passive"))
      (node (ref "E23") (pin "16") (pinfunction "16_16") (pintype "passive"))
      (node (ref "E24") (pin "15") (pinfunction "15_15") (pintype "passive"))
      (node (ref "E24") (pin "16") (pinfunction "16_16") (pintype "passive"))
      (node (ref "E3") (pin "15") (pinfunction "15_15") (pintype "passive"))
      (node (ref "E3") (pin "16") (pinfunction "16_16") (pintype "passive"))
      (node (ref "E4") (pin "15") (pinfunction "15_15") (pintype "passive"))
      (node (ref "E4") (pin "16") (pinfunction "16_16") (pintype "passive"))
      (node (ref "E5") (pin "15") (pinfunction "15_15") (pintype "passive"))
      (node (ref "E5") (pin "16") (pinfunction "16_16") (pintype "passive"))
      (node (ref "E6") (pin "15") (pinfunction "15_15") (pintype "passive"))
      (node (ref "E6") (pin "16") (pinfunction "16_16") (pintype "passive"))
      (node (ref "E7") (pin "15") (pinfunction "15_15") (pintype "passive"))
      (node (ref "E7") (pin "16") (pinfunction "16_16") (pintype "passive"))
      (node (ref "E8") (pin "15") (pinfunction "15_15") (pintype "passive"))
      (node (ref "E8") (pin "16") (pinfunction "16_16") (pintype "passive"))
      (node (ref "E9") (pin "15") (pinfunction "15_15") (pintype "passive"))
      (node (ref "E9") (pin "16") (pinfunction "16_16") (pintype "passive"))
    )
    (net (code "6") (name "GND") (class "Default")
      (node (ref "C4") (pin "2") (pinfunction "-_2") (pintype "bidirectional"))
      (node (ref "C5") (pin "1") (pinfunction "+_1") (pintype "bidirectional"))
      (node (ref "C6") (pin "1") (pinfunction "+_1") (pintype "bidirectional"))
      (node (ref "C7") (pin "2") (pinfunction "-_2") (pintype "bidirectional"))
      (node (ref "C9") (pin "2") (pinfunction "-_2") (pintype "bidirectional"))
      (node (ref "E1") (pin "3") (pinfunction "3_3") (pintype "passive"))
      (node (ref "E1") (pin "4") (pinfunction "4_4") (pintype "passive"))
      (node (ref "E1") (pin "5") (pinfunction "5_5") (pintype "passive"))
      (node (ref "E1") (pin "6") (pinfunction "6_6") (pintype "passive"))
      (node (ref "E1") (pin "7") (pinfunction "7_7") (pintype "passive"))
      (node (ref "E1") (pin "8") (pinfunction "8_8") (pintype "passive"))
      (node (ref "E10") (pin "3") (pinfunction "3_3") (pintype "passive"))
      (node (ref "E10") (pin "4") (pinfunction "4_4") (pintype "passive"))
      (node (ref "E10") (pin "5") (pinfunction "5_5") (pintype "passive"))
      (node (ref "E10") (pin "6") (pinfunction "6_6") (pintype "passive"))
      (node (ref "E10") (pin "7") (pinfunction "7_7") (pintype "passive"))
      (node (ref "E10") (pin "8") (pinfunction "8_8") (pintype "passive"))
      (node (ref "E11") (pin "3") (pinfunction "3_3") (pintype "passive"))
      (node (ref "E11") (pin "4") (pinfunction "4_4") (pintype "passive"))
      (node (ref "E11") (pin "5") (pinfunction "5_5") (pintype "passive"))
      (node (ref "E11") (pin "6") (pinfunction "6_6") (pintype "passive"))
      (node (ref "E11") (pin "7") (pinfunction "7_7") (pintype "passive"))
      (node (ref "E11") (pin "8") (pinfunction "8_8") (pintype "passive"))
      (node (ref "E12") (pin "3") (pinfunction "3_3") (pintype "passive"))
      (node (ref "E12") (pin "4") (pinfunction "4_4") (pintype "passive"))
      (node (ref "E12") (pin "5") (pinfunction "5_5") (pintype "passive"))
      (node (ref "E12") (pin "6") (pinfunction "6_6") (pintype "passive"))
      (node (ref "E12") (pin "7") (pinfunction "7_7") (pintype "passive"))
      (node (ref "E12") (pin "8") (pinfunction "8_8") (pintype "passive"))
      (node (ref "E13") (pin "3") (pinfunction "3_3") (pintype "passive"))
      (node (ref "E13") (pin "4") (pinfunction "4_4") (pintype "passive"))
      (node (ref "E13") (pin "5") (pinfunction "5_5") (pintype "passive"))
      (node (ref "E13") (pin "6") (pinfunction "6_6") (pintype "passive"))
      (node (ref "E13") (pin "7") (pinfunction "7_7") (pintype "passive"))
      (node (ref "E13") (pin "8") (pinfunction "8_8") (pintype "passive"))
      (node (ref "E14") (pin "3") (pinfunction "3_3") (pintype "passive"))
      (node (ref "E14") (pin "4") (pinfunction "4_4") (pintype "passive"))
      (node (ref "E14") (pin "5") (pinfunction "5_5") (pintype "passive"))
      (node (ref "E14") (pin "6") (pinfunction "6_6") (pintype "passive"))
      (node (ref "E14") (pin "7") (pinfunction "7_7") (pintype "passive"))
      (node (ref "E14") (pin "8") (pinfunction "8_8") (pintype "passive"))
      (node (ref "E15") (pin "3") (pinfunction "3_3") (pintype "passive"))
      (node (ref "E15") (pin "4") (pinfunction "4_4") (pintype "passive"))
      (node (ref "E15") (pin "5") (pinfunction "5_5") (pintype "passive"))
      (node (ref "E15") (pin "6") (pinfunction "6_6") (pintype "passive"))
      (node (ref "E15") (pin "7") (pinfunction "7_7") (pintype "passive"))
      (node (ref "E15") (pin "8") (pinfunction "8_8") (pintype "passive"))
      (node (ref "E16") (pin "3") (pinfunction "3_3") (pintype "passive"))
      (node (ref "E16") (pin "4") (pinfunction "4_4") (pintype "passive"))
      (node (ref "E16") (pin "5") (pinfunction "5_5") (pintype "passive"))
      (node (ref "E16") (pin "6") (pinfunction "6_6") (pintype "passive"))
      (node (ref "E16") (pin "7") (pinfunction "7_7") (pintype "passive"))
      (node (ref "E16") (pin "8") (pinfunction "8_8") (pintype "passive"))
      (node (ref "E17") (pin "3") (pinfunction "3_3") (pintype "passive"))
      (node (ref "E17") (pin "4") (pinfunction "4_4") (pintype "passive"))
      (node (ref "E17") (pin "5") (pinfunction "5_5") (pintype "passive"))
      (node (ref "E17") (pin "6") (pinfunction "6_6") (pintype "passive"))
      (node (ref "E17") (pin "7") (pinfunction "7_7") (pintype "passive"))
      (node (ref "E17") (pin "8") (pinfunction "8_8") (pintype "passive"))
      (node (ref "E18") (pin "3") (pinfunction "3_3") (pintype "passive"))
      (node (ref "E18") (pin "4") (pinfunction "4_4") (pintype "passive"))
      (node (ref "E18") (pin "5") (pinfunction "5_5") (pintype "passive"))
      (node (ref "E18") (pin "6") (pinfunction "6_6") (pintype "passive"))
      (node (ref "E18") (pin "7") (pinfunction "7_7") (pintype "passive"))
      (node (ref "E18") (pin "8") (pinfunction "8_8") (pintype "passive"))
      (node (ref "E19") (pin "3") (pinfunction "3_3") (pintype "passive"))
      (node (ref "E19") (pin "4") (pinfunction "4_4") (pintype "passive"))
      (node (ref "E19") (pin "5") (pinfunction "5_5") (pintype "passive"))
      (node (ref "E19") (pin "6") (pinfunction "6_6") (pintype "passive"))
      (node (ref "E19") (pin "7") (pinfunction "7_7") (pintype "passive"))
      (node (ref "E19") (pin "8") (pinfunction "8_8") (pintype "passive"))
      (node (ref "E2") (pin "3") (pinfunction "3_3") (pintype "passive"))
      (node (ref "E2") (pin "4") (pinfunction "4_4") (pintype "passive"))
      (node (ref "E2") (pin "5") (pinfunction "5_5") (pintype "passive"))
      (node (ref "E2") (pin "6") (pinfunction "6_6") (pintype "passive"))
      (node (ref "E2") (pin "7") (pinfunction "7_7") (pintype "passive"))
      (node (ref "E2") (pin "8") (pinfunction "8_8") (pintype "passive"))
      (node (ref "E20") (pin "3") (pinfunction "3_3") (pintype "passive"))
      (node (ref "E20") (pin "4") (pinfunction "4_4") (pintype "passive"))
      (node (ref "E20") (pin "5") (pinfunction "5_5") (pintype "passive"))
      (node (ref "E20") (pin "6") (pinfunction "6_6") (pintype "passive"))
      (node (ref "E20") (pin "7") (pinfunction "7_7") (pintype "passive"))
      (node (ref "E20") (pin "8") (pinfunction "8_8") (pintype "passive"))
      (node (ref "E21") (pin "3") (pinfunction "3_3") (pintype "passive"))
      (node (ref "E21") (pin "4") (pinfunction "4_4") (pintype "passive"))
      (node (ref "E21") (pin "5") (pinfunction "5_5") (pintype "passive"))
      (node (ref "E21") (pin "6") (pinfunction "6_6") (pintype "passive"))
      (node (ref "E21") (pin "7") (pinfunction "7_7") (pintype "passive"))
      (node (ref "E21") (pin "8") (pinfunction "8_8") (pintype "passive"))
      (node (ref "E22") (pin "3") (pinfunction "3_3") (pintype "passive"))
      (node (ref "E22") (pin "4") (pinfunction "4_4") (pintype "passive"))
      (node (ref "E22") (pin "5") (pinfunction "5_5") (pintype "passive"))
      (node (ref "E22") (pin "6") (pinfunction "6_6") (pintype "passive"))
      (node (ref "E22") (pin "7") (pinfunction "7_7") (pintype "passive"))
      (node (ref "E22") (pin "8") (pinfunction "8_8") (pintype "passive"))
      (node (ref "E23") (pin "3") (pinfunction "3_3") (pintype "passive"))
      (node (ref "E23") (pin "4") (pinfunction "4_4") (pintype "passive"))
      (node (ref "E23") (pin "5") (pinfunction "5_5") (pintype "passive"))
      (node (ref "E23") (pin "6") (pinfunction "6_6") (pintype "passive"))
      (node (ref "E23") (pin "7") (pinfunction "7_7") (pintype "passive"))
      (node (ref "E23") (pin "8") (pinfunction "8_8") (pintype "passive"))
      (node (ref "E24") (pin "3") (pinfunction "3_3") (pintype "passive"))
      (node (ref "E24") (pin "4") (pinfunction "4_4") (pintype "passive"))
      (node (ref "E24") (pin "5") (pinfunction "5_5") (pintype "passive"))
      (node (ref "E24") (pin "6") (pinfunction "6_6") (pintype "passive"))
      (node (ref "E24") (pin "7") (pinfunction "7_7") (pintype "passive"))
      (node (ref "E24") (pin "8") (pinfunction "8_8") (pintype "passive"))
      (node (ref "E3") (pin "3") (pinfunction "3_3") (pintype "passive"))
      (node (ref "E3") (pin "4") (pinfunction "4_4") (pintype "passive"))
      (node (ref "E3") (pin "5") (pinfunction "5_5") (pintype "passive"))
      (node (ref "E3") (pin "6") (pinfunction "6_6") (pintype "passive"))
      (node (ref "E3") (pin "7") (pinfunction "7_7") (pintype "passive"))
      (node (ref "E3") (pin "8") (pinfunction "8_8") (pintype "passive"))
      (node (ref "E4") (pin "3") (pinfunction "3_3") (pintype "passive"))
      (node (ref "E4") (pin "4") (pinfunction "4_4") (pintype "passive"))
      (node (ref "E4") (pin "5") (pinfunction "5_5") (pintype "passive"))
      (node (ref "E4") (pin "6") (pinfunction "6_6") (pintype "passive"))
      (node (ref "E4") (pin "7") (pinfunction "7_7") (pintype "passive"))
      (node (ref "E4") (pin "8") (pinfunction "8_8") (pintype "passive"))
      (node (ref "E5") (pin "3") (pinfunction "3_3") (pintype "passive"))
      (node (ref "E5") (pin "4") (pinfunction "4_4") (pintype "passive"))
      (node (ref "E5") (pin "5") (pinfunction "5_5") (pintype "passive"))
      (node (ref "E5") (pin "6") (pinfunction "6_6") (pintype "passive"))
      (node (ref "E5") (pin "7") (pinfunction "7_7") (pintype "passive"))
      (node (ref "E5") (pin "8") (pinfunction "8_8") (pintype "passive"))
      (node (ref "E6") (pin "3") (pinfunction "3_3") (pintype "passive"))
      (node (ref "E6") (pin "4") (pinfunction "4_4") (pintype "passive"))
      (node (ref "E6") (pin "5") (pinfunction "5_5") (pintype "passive"))
      (node (ref "E6") (pin "6") (pinfunction "6_6") (pintype "passive"))
      (node (ref "E6") (pin "7") (pinfunction "7_7") (pintype "passive"))
      (node (ref "E6") (pin "8") (pinfunction "8_8") (pintype "passive"))
      (node (ref "E7") (pin "3") (pinfunction "3_3") (pintype "passive"))
      (node (ref "E7") (pin "4") (pinfunction "4_4") (pintype "passive"))
      (node (ref "E7") (pin "5") (pinfunction "5_5") (pintype "passive"))
      (node (ref "E7") (pin "6") (pinfunction "6_6") (pintype "passive"))
      (node (ref "E7") (pin "7") (pinfunction "7_7") (pintype "passive"))
      (node (ref "E7") (pin "8") (pinfunction "8_8") (pintype "passive"))
      (node (ref "E8") (pin "3") (pinfunction "3_3") (pintype "passive"))
      (node (ref "E8") (pin "4") (pinfunction "4_4") (pintype "passive"))
      (node (ref "E8") (pin "5") (pinfunction "5_5") (pintype "passive"))
      (node (ref "E8") (pin "6") (pinfunction "6_6") (pintype "passive"))
      (node (ref "E8") (pin "7") (pinfunction "7_7") (pintype "passive"))
      (node (ref "E8") (pin "8") (pinfunction "8_8") (pintype "passive"))
      (node (ref "E9") (pin "3") (pinfunction "3_3") (pintype "passive"))
      (node (ref "E9") (pin "4") (pinfunction "4_4") (pintype "passive"))
      (node (ref "E9") (pin "5") (pinfunction "5_5") (pintype "passive"))
      (node (ref "E9") (pin "6") (pinfunction "6_6") (pintype "passive"))
      (node (ref "E9") (pin "7") (pinfunction "7_7") (pintype "passive"))
      (node (ref "E9") (pin "8") (pinfunction "8_8") (pintype "passive"))
      (node (ref "J1") (pin "2") (pinfunction "2_2") (pintype "bidirectional"))
      (node (ref "J10") (pin "4") (pinfunction "4_4") (pintype "bidirectional"))
      (node (ref "J11") (pin "4") (pinfunction "4_4") (pintype "bidirectional"))
      (node (ref "J12") (pin "4") (pinfunction "4_4") (pintype "bidirectional"))
      (node (ref "J13") (pin "4") (pinfunction "4_4") (pintype "bidirectional"))
      (node (ref "J14") (pin "3") (pinfunction "3_3") (pintype "passive"))
      (node (ref "J14") (pin "4") (pinfunction "4_4") (pintype "passive"))
      (node (ref "J14") (pin "5") (pinfunction "5_5") (pintype "passive"))
      (node (ref "J14") (pin "6") (pinfunction "6_6") (pintype "passive"))
      (node (ref "J14") (pin "7") (pinfunction "7_7") (pintype "passive"))
      (node (ref "J14") (pin "8") (pinfunction "8_8") (pintype "passive"))
      (node (ref "J15") (pin "3") (pinfunction "3_3") (pintype "passive"))
      (node (ref "J15") (pin "4") (pinfunction "4_4") (pintype "passive"))
      (node (ref "J15") (pin "5") (pinfunction "5_5") (pintype "passive"))
      (node (ref "J15") (pin "6") (pinfunction "6_6") (pintype "passive"))
      (node (ref "J15") (pin "7") (pinfunction "7_7") (pintype "passive"))
      (node (ref "J15") (pin "8") (pinfunction "8_8") (pintype "passive"))
      (node (ref "J16") (pin "4") (pinfunction "4_4") (pintype "bidirectional"))
      (node (ref "J3") (pin "4") (pinfunction "4_4") (pintype "bidirectional"))
      (node (ref "J4") (pin "4") (pinfunction "4_4") (pintype "bidirectional"))
      (node (ref "J5") (pin "4") (pinfunction "4_4") (pintype "bidirectional"))
      (node (ref "J6") (pin "4") (pinfunction "4_4") (pintype "bidirectional"))
      (node (ref "J7") (pin "4") (pinfunction "4_4") (pintype "bidirectional"))
      (node (ref "J8") (pin "4") (pinfunction "4_4") (pintype "bidirectional"))
      (node (ref "J9") (pin "4") (pinfunction "4_4") (pintype "bidirectional"))
      (node (ref "PS1") (pin "1") (pinfunction "GND_1") (pintype "power_in"))
      (node (ref "R2") (pin "2") (pinfunction "2_2") (pintype "passive"))
      (node (ref "U1") (pin "1") (pinfunction "GND_1") (pintype "bidirectional"))
    )
    (net (code "7") (name "Net-(BR1-~{_1})") (class "Default")
      (node (ref "BR1") (pin "2") (pinfunction "~{_1}_2") (pintype "bidirectional"))
      (node (ref "J1") (pin "1") (pinfunction "1_1") (pintype "bidirectional"))
    )
    (net (code "8") (name "Net-(BR1-~{_2})") (class "Default")
      (node (ref "BR1") (pin "3") (pinfunction "~{_2}_3") (pintype "bidirectional"))
      (node (ref "J1") (pin "3") (pinfunction "3_3") (pintype "bidirectional"))
    )
    (net (code "9") (name "Net-(C8--)") (class "Default")
      (node (ref "C8") (pin "2") (pinfunction "-_2") (pintype "bidirectional"))
      (node (ref "IC1") (pin "1") (pinfunction "ADJ/GND_1") (pintype "bidirectional"))
      (node (ref "R1") (pin "2") (pinfunction "2_2") (pintype "passive"))
      (node (ref "R2") (pin "1") (pinfunction "1_1") (pintype "passive"))
    )
    (net (code "10") (name "UNREG_+V") (class "Default")
      (node (ref "BR1") (pin "1") (pinfunction "+_1") (pintype "bidirectional"))
      (node (ref "C1") (pin "1") (pinfunction "+_1") (pintype "bidirectional"))
      (node (ref "C2") (pin "1") (pinfunction "+_1") (pintype "bidirectional"))
      (node (ref "C3") (pin "1") (pinfunction "+_1") (pintype "bidirectional"))
      (node (ref "C7") (pin "1") (pinfunction "+_1") (pintype "bidirectional"))
      (node (ref "C9") (pin "1") (pinfunction "+_1") (pintype "bidirectional"))
      (node (ref "IC1") (pin "3") (pinfunction "INPUT_3") (pintype "bidirectional"))
      (node (ref "PS1") (pin "3") (pinfunction "INPUT_3") (pintype "input"))
    )
    (net (code "11") (name "UNREG_-V") (class "Default")
      (node (ref "BR1") (pin "4") (pinfunction "-_4") (pintype "bidirectional"))
      (node (ref "C1") (pin "2") (pinfunction "-_2") (pintype "bidirectional"))
      (node (ref "C2") (pin "2") (pinfunction "-_2") (pintype "bidirectional"))
      (node (ref "C3") (pin "2") (pinfunction "-_2") (pintype "bidirectional"))
      (node (ref "C5") (pin "2") (pinfunction "-_2") (pintype "bidirectional"))
      (node (ref "U1") (pin "2") (pinfunction "IN_2") (pintype "bidirectional"))
    )
    (net (code "12") (name "unconnected-(J3-Pad2)") (class "Default")
      (node (ref "J3") (pin "2") (pinfunction "2_2") (pintype "bidirectional"))
    )
    (net (code "13") (name "unconnected-(J3-Pad6)") (class "Default")
      (node (ref "J3") (pin "6") (pinfunction "6_6") (pintype "bidirectional"))
    )
    (net (code "14") (name "unconnected-(J4-Pad2)") (class "Default")
      (node (ref "J4") (pin "2") (pinfunction "2_2") (pintype "bidirectional"))
    )
    (net (code "15") (name "unconnected-(J4-Pad6)") (class "Default")
      (node (ref "J4") (pin "6") (pinfunction "6_6") (pintype "bidirectional"))
    )
    (net (code "16") (name "unconnected-(J5-Pad2)") (class "Default")
      (node (ref "J5") (pin "2") (pinfunction "2_2") (pintype "bidirectional"))
    )
    (net (code "17") (name "unconnected-(J5-Pad6)") (class "Default")
      (node (ref "J5") (pin "6") (pinfunction "6_6") (pintype "bidirectional"))
    )
    (net (code "18") (name "unconnected-(J6-Pad2)") (class "Default")
      (node (ref "J6") (pin "2") (pinfunction "2_2") (pintype "bidirectional"))
    )
    (net (code "19") (name "unconnected-(J6-Pad6)") (class "Default")
      (node (ref "J6") (pin "6") (pinfunction "6_6") (pintype "bidirectional"))
    )
    (net (code "20") (name "unconnected-(J7-Pad2)") (class "Default")
      (node (ref "J7") (pin "2") (pinfunction "2_2") (pintype "bidirectional"))
    )
    (net (code "21") (name "unconnected-(J7-Pad6)") (class "Default")
      (node (ref "J7") (pin "6") (pinfunction "6_6") (pintype "bidirectional"))
    )
    (net (code "22") (name "unconnected-(J8-Pad2)") (class "Default")
      (node (ref "J8") (pin "2") (pinfunction "2_2") (pintype "bidirectional"))
    )
    (net (code "23") (name "unconnected-(J8-Pad6)") (class "Default")
      (node (ref "J8") (pin "6") (pinfunction "6_6") (pintype "bidirectional"))
    )
    (net (code "24") (name "unconnected-(J9-Pad2)") (class "Default")
      (node (ref "J9") (pin "2") (pinfunction "2_2") (pintype "bidirectional"))
    )
    (net (code "25") (name "unconnected-(J9-Pad6)") (class "Default")
      (node (ref "J9") (pin "6") (pinfunction "6_6") (pintype "bidirectional"))
    )
    (net (code "26") (name "unconnected-(J10-Pad2)") (class "Default")
      (node (ref "J10") (pin "2") (pinfunction "2_2") (pintype "bidirectional"))
    )
    (net (code "27") (name "unconnected-(J10-Pad6)") (class "Default")
      (node (ref "J10") (pin "6") (pinfunction "6_6") (pintype "bidirectional"))
    )
    (net (code "28") (name "unconnected-(J11-Pad2)") (class "Default")
      (node (ref "J11") (pin "2") (pinfunction "2_2") (pintype "bidirectional"))
    )
    (net (code "29") (name "unconnected-(J11-Pad6)") (class "Default")
      (node (ref "J11") (pin "6") (pinfunction "6_6") (pintype "bidirectional"))
    )
    (net (code "30") (name "unconnected-(J12-Pad2)") (class "Default")
      (node (ref "J12") (pin "2") (pinfunction "2_2") (pintype "bidirectional"))
    )
    (net (code "31") (name "unconnected-(J12-Pad6)") (class "Default")
      (node (ref "J12") (pin "6") (pinfunction "6_6") (pintype "bidirectional"))
    )
    (net (code "32") (name "unconnected-(J13-Pad2)") (class "Default")
      (node (ref "J13") (pin "2") (pinfunction "2_2") (pintype "bidirectional"))
    )
    (net (code "33") (name "unconnected-(J13-Pad6)") (class "Default")
      (node (ref "J13") (pin "6") (pinfunction "6_6") (pintype "bidirectional"))
    )
    (net (code "34") (name "unconnected-(J16-Pad2)") (class "Default")
      (node (ref "J16") (pin "2") (pinfunction "2_2") (pintype "bidirectional"))
    )
    (net (code "35") (name "unconnected-(J16-Pad6)") (class "Default")
      (node (ref "J16") (pin "6") (pinfunction "6_6") (pintype "bidirectional"))
    )
  )
)
